# ProPrj___2025-10-04.net
KiCad netlist of a schematic drawn in EasyEDA Pro
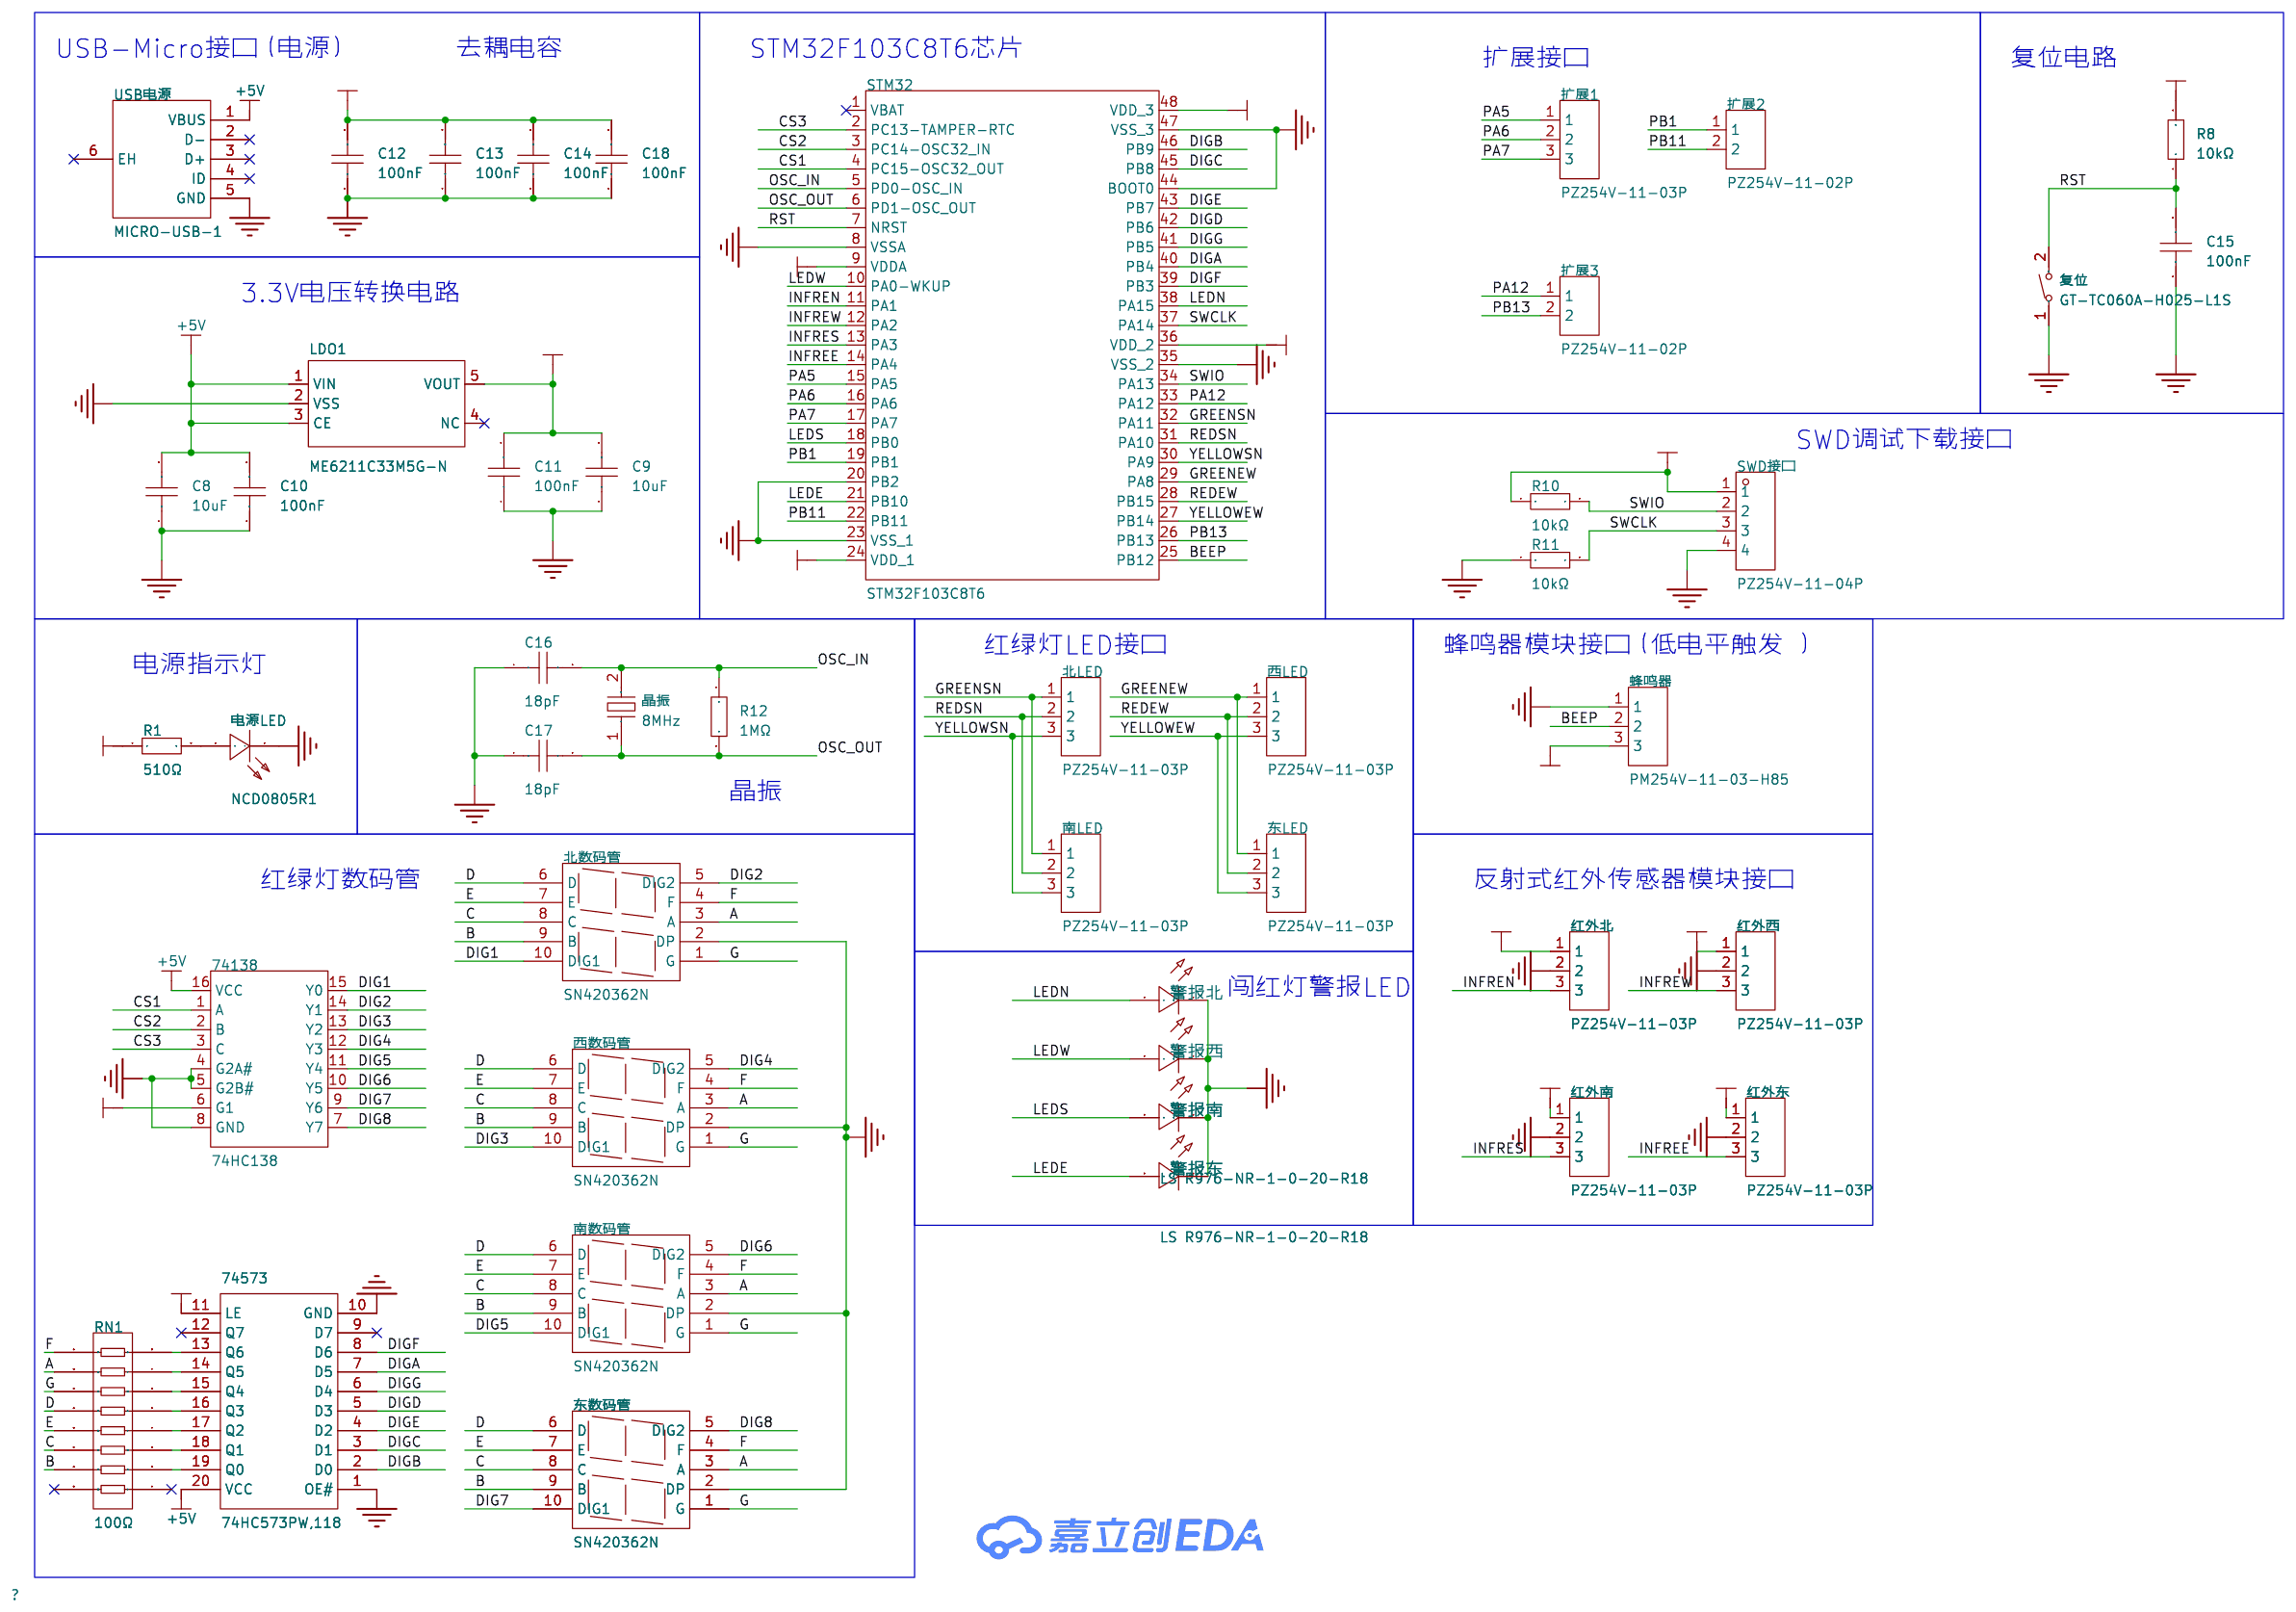
[diagram p0: schematic sheet]

(export (version "E")
  (design (tool "Eeschema 10.0.6"))
  (components
    (comp (ref "74138")
      (value "74HC138")
      (footprint "easyedapro:SOP-16_L10.0-W3.9-P1.27-LS6.0-BL")
      (description "供电电压:2V~6V;线路数:3~8;灌电流(IOL):5.2mA;拉电流(IOH):5.2mA;")
      (fields (field (name "Manufacturer") "GR(国睿)"))
      (libsource (lib "easyedapro") (part "74HC138_C18164491"))
    )
    (comp (ref "74573")
      (value "74HC573PW,118")
      (footprint "easyedapro:TSSOP-20_L6.5-W4.4-P0.65-LS6.4-BL")
      (description "逻辑类型:D型锁存器;电源电压:2V~6V;通道数:8;传播延迟:14ns;")
      (fields (field (name "Manufacturer") "Nexperia(安世)"))
      (libsource (lib "easyedapro") (part "74HC573PW,118"))
    )
    (comp (ref "C8")
      (value "10uF")
      (footprint "easyedapro:C0805")
      (description "容值:10uF;精度:±10%;额定电压:25V;温度系数:X5R;")
      (fields
        (field (name "Manufacturer Part") "CGA0805X5R106K250MT")
        (field (name "Manufacturer") "HRE(芯声)")
      )
      (libsource (lib "easyedapro") (part "CGA0805X5R106K250MT"))
    )
    (comp (ref "C9")
      (value "10uF")
      (footprint "easyedapro:C0805")
      (description "容值:10uF;精度:±10%;额定电压:25V;温度系数:X5R;")
      (fields
        (field (name "Manufacturer Part") "CGA0805X5R106K250MT")
        (field (name "Manufacturer") "HRE(芯声)")
      )
      (libsource (lib "easyedapro") (part "CGA0805X5R106K250MT"))
    )
    (comp (ref "C10")
      (value "100nF")
      (footprint "easyedapro:C0805")
      (description "容值:100nF;精度:±10%;额定电压:50V;材质(温度系数):X7R;")
      (fields
        (field (name "Manufacturer Part") "CC0805KRX7R9BB104")
        (field (name "Manufacturer") "YAGEO(国巨)")
      )
      (libsource (lib "easyedapro") (part "CC0805KRX7R9BB104"))
    )
    (comp (ref "C11")
      (value "100nF")
      (footprint "easyedapro:C0805")
      (description "容值:100nF;精度:±10%;额定电压:50V;材质(温度系数):X7R;")
      (fields
        (field (name "Manufacturer Part") "CC0805KRX7R9BB104")
        (field (name "Manufacturer") "YAGEO(国巨)")
      )
      (libsource (lib "easyedapro") (part "CC0805KRX7R9BB104"))
    )
    (comp (ref "C12")
      (value "100nF")
      (footprint "easyedapro:C0805")
      (description "容值:100nF;精度:±10%;额定电压:50V;材质(温度系数):X7R;")
      (fields
        (field (name "Manufacturer Part") "CC0805KRX7R9BB104")
        (field (name "Manufacturer") "YAGEO(国巨)")
      )
      (libsource (lib "easyedapro") (part "CC0805KRX7R9BB104"))
    )
    (comp (ref "C13")
      (value "100nF")
      (footprint "easyedapro:C0805")
      (description "容值:100nF;精度:±10%;额定电压:50V;材质(温度系数):X7R;")
      (fields
        (field (name "Manufacturer Part") "CC0805KRX7R9BB104")
        (field (name "Manufacturer") "YAGEO(国巨)")
      )
      (libsource (lib "easyedapro") (part "CC0805KRX7R9BB104"))
    )
    (comp (ref "C14")
      (value "100nF")
      (footprint "easyedapro:C0805")
      (description "容值:100nF;精度:±10%;额定电压:50V;材质(温度系数):X7R;")
      (fields
        (field (name "Manufacturer Part") "CC0805KRX7R9BB104")
        (field (name "Manufacturer") "YAGEO(国巨)")
      )
      (libsource (lib "easyedapro") (part "CC0805KRX7R9BB104"))
    )
    (comp (ref "C15")
      (value "100nF")
      (footprint "easyedapro:C0805")
      (description "容值:100nF;精度:±10%;额定电压:50V;材质(温度系数):X7R;")
      (fields
        (field (name "Manufacturer Part") "CC0805KRX7R9BB104")
        (field (name "Manufacturer") "YAGEO(国巨)")
      )
      (libsource (lib "easyedapro") (part "CC0805KRX7R9BB104"))
    )
    (comp (ref "C16")
      (value "18pF")
      (footprint "easyedapro:C0805")
      (description "容值:18pF;精度:±5%;额定电压:50V;温度系数:C0G;")
      (fields
        (field (name "Manufacturer Part") "CGA0805C0G180J500HT")
        (field (name "Manufacturer") "HRE(芯声)")
      )
      (libsource (lib "easyedapro") (part "CGA0805C0G180J500HT"))
    )
    (comp (ref "C17")
      (value "18pF")
      (footprint "easyedapro:C0805")
      (description "容值:18pF;精度:±5%;额定电压:50V;温度系数:C0G;")
      (fields
        (field (name "Manufacturer Part") "CGA0805C0G180J500HT")
        (field (name "Manufacturer") "HRE(芯声)")
      )
      (libsource (lib "easyedapro") (part "CGA0805C0G180J500HT"))
    )
    (comp (ref "C18")
      (value "100nF")
      (footprint "easyedapro:C0805")
      (description "容值:100nF;精度:±10%;额定电压:50V;材质(温度系数):X7R;")
      (fields
        (field (name "Manufacturer Part") "CC0805KRX7R9BB104")
        (field (name "Manufacturer") "YAGEO(国巨)")
      )
      (libsource (lib "easyedapro") (part "CC0805KRX7R9BB104"))
    )
    (comp (ref "LDO1")
      (value "ME6211C33M5G-N")
      (footprint "easyedapro:SOT-23-5_L3.0-W1.7-P0.95-LS2.8-BL")
      (description "输出类型:固定;工作电压:6V;输出电压:3.3V;输出电流:500mA;电源纹波抑制比(PSRR):70dB@(1kHz)；62dB@(10kHz);输出极性:正极;")
      (fields (field (name "Manufacturer") "MICRONE(南京微盟)"))
      (libsource (lib "easyedapro") (part "ME6211C33M5G-N"))
    )
    (comp (ref "R1")
      (value "510Ω")
      (footprint "easyedapro:R0805")
      (description "电阻类型:厚膜电阻;阻值:510Ω;精度:±1%;功率:125mW;最大工作电压:150V;温度系数:±100ppm/°C;")
      (fields
        (field (name "Manufacturer Part") "0805W8F5100T5E")
        (field (name "Manufacturer") "UNI-ROYAL(厚声)")
      )
      (libsource (lib "easyedapro") (part "0805W8F5100T5E"))
    )
    (comp (ref "R8")
      (value "10kΩ")
      (footprint "easyedapro:R0805")
      (description "电阻类型:厚膜电阻;阻值:10kΩ;精度:±1%;功率:125mW;最大工作电压:150V;温度系数:±100ppm/°C;")
      (fields
        (field (name "Manufacturer Part") "0805W8F1002T5E")
        (field (name "Manufacturer") "UNI-ROYAL(厚声)")
      )
      (libsource (lib "easyedapro") (part "0805W8F1002T5E"))
    )
    (comp (ref "R10")
      (value "10kΩ")
      (footprint "easyedapro:R0805")
      (description "电阻类型:厚膜电阻;阻值:10kΩ;精度:±1%;功率:125mW;最大工作电压:150V;温度系数:±100ppm/°C;")
      (fields
        (field (name "Manufacturer Part") "0805W8F1002T5E")
        (field (name "Manufacturer") "UNI-ROYAL(厚声)")
      )
      (libsource (lib "easyedapro") (part "0805W8F1002T5E"))
    )
    (comp (ref "R11")
      (value "10kΩ")
      (footprint "easyedapro:R0805")
      (description "电阻类型:厚膜电阻;阻值:10kΩ;精度:±1%;功率:125mW;最大工作电压:150V;温度系数:±100ppm/°C;")
      (fields
        (field (name "Manufacturer Part") "0805W8F1002T5E")
        (field (name "Manufacturer") "UNI-ROYAL(厚声)")
      )
      (libsource (lib "easyedapro") (part "0805W8F1002T5E"))
    )
    (comp (ref "R12")
      (value "1MΩ")
      (footprint "easyedapro:R0805")
      (description "电阻类型:厚膜电阻;阻值:1MΩ;精度:±1%;功率:125mW;最大工作电压:150V;温度系数:±100ppm/°C;")
      (fields
        (field (name "Manufacturer Part") "0805W8F1004T5E")
        (field (name "Manufacturer") "UNI-ROYAL(厚声)")
      )
      (libsource (lib "easyedapro") (part "0805W8F1004T5E"))
    )
    (comp (ref "RN1")
      (value "100Ω")
      (footprint "easyedapro:RES-ARRAY-SMD_16P-L3.8-W1.6-P0.50-BL")
      (description "电阻器数:8;阻值:100Ω;精度:±5%;单个元件功率:63mW;温度系数:±100ppm/°C;")
      (fields (field (name "Manufacturer Part") "EXB2HV101JV") (field (name "Manufacturer") "PANASONIC(松下)"))
      (libsource (lib "easyedapro") (part "EXB2HV101JV"))
    )
    (comp (ref "STM32")
      (value "STM32F103C8T6")
      (footprint "easyedapro:LQFP-48_L7.0-W7.0-P0.50-LS9.0-BL")
      (description "CPU内核:ARM-M3;CPU最大主频:72MHz;应用领域:-;")
      (fields (field (name "Manufacturer") "ST(意法半导体)"))
      (libsource (lib "easyedapro") (part "STM32F103C8T6"))
    )
    (comp (ref "SWD接口")
      (value "PZ254V-11-04P")
      (footprint "easyedapro:HDR-TH_4P-P2.54-V-M")
      (fields (field (name "Manufacturer") "XFCN(兴飞)"))
      (libsource (lib "easyedapro") (part "PZ254V-11-04P_C2691448"))
    )
    (comp (ref "USB电源")
      (value "MICRO-USB-1")
      (footprint "easyedapro:MICRO-USB-SMD_C9900008946")
      (libsource (lib "easyedapro") (part "MICRO-USB-1"))
    )
    (comp (ref "东LED")
      (value "PZ254V-11-03P")
      (footprint "easyedapro:HDR-TH_3P-P2.54-V-M")
      (fields (field (name "Manufacturer") "XFCN(兴飞)"))
      (libsource (lib "easyedapro") (part "PZ254V-11-03P_C2937625"))
    )
    (comp (ref "东数码管")
      (value "SN420362N")
      (footprint "easyedapro:LED-SEG-TH_10P-L15.0-W14.0-P2.54-S10.16-BL")
      (description "数码管位数:2位;耗散功率(Pd):50mW;发光颜色:红色;LED极性:共阴极;数字/字母大小(英寸):0.36;")
      (fields (field (name "Manufacturer") "ARKLED(方舟)"))
      (libsource (lib "easyedapro") (part "SN420362N"))
    )
    (comp (ref "北LED")
      (value "PZ254V-11-03P")
      (footprint "easyedapro:HDR-TH_3P-P2.54-V-M")
      (fields (field (name "Manufacturer") "XFCN(兴飞)"))
      (libsource (lib "easyedapro") (part "PZ254V-11-03P_C2937625"))
    )
    (comp (ref "北数码管")
      (value "SN420362N")
      (footprint "easyedapro:LED-SEG-TH_10P-L15.0-W14.0-P2.54-S10.16-BL")
      (description "数码管位数:2位;耗散功率(Pd):50mW;发光颜色:红色;LED极性:共阴极;数字/字母大小(英寸):0.36;")
      (fields (field (name "Manufacturer") "ARKLED(方舟)"))
      (libsource (lib "easyedapro") (part "SN420362N"))
    )
    (comp (ref "南LED")
      (value "PZ254V-11-03P")
      (footprint "easyedapro:HDR-TH_3P-P2.54-V-M")
      (fields (field (name "Manufacturer") "XFCN(兴飞)"))
      (libsource (lib "easyedapro") (part "PZ254V-11-03P_C2937625"))
    )
    (comp (ref "南数码管")
      (value "SN420362N")
      (footprint "easyedapro:LED-SEG-TH_10P-L15.0-W14.0-P2.54-S10.16-BL")
      (description "数码管位数:2位;耗散功率(Pd):50mW;发光颜色:红色;LED极性:共阴极;数字/字母大小(英寸):0.36;")
      (fields (field (name "Manufacturer") "ARKLED(方舟)"))
      (libsource (lib "easyedapro") (part "SN420362N"))
    )
    (comp (ref "复位")
      (value "GT-TC060A-H025-L1S")
      (footprint "easyedapro:SW-SMD_L6.1-W3.5-LS8.0")
      (description "电路结构:单刀单掷;作用力:1.6N;安装方式:立贴;带支架:不带;触点电流:50mA;额定电压(AC):12V;额定电压(DC):12V;绝缘电阻:100MΩ;带灯:无;机械寿命:10万次;")
      (fields (field (name "Manufacturer") "G-Switch(品赞)"))
      (libsource (lib "easyedapro") (part "GT-TC060A-H025-L1S"))
    )
    (comp (ref "扩展1")
      (value "PZ254V-11-03P")
      (footprint "easyedapro:HDR-TH_3P-P2.54-V-M")
      (fields (field (name "Manufacturer") "XFCN(兴飞)"))
      (libsource (lib "easyedapro") (part "PZ254V-11-03P_C2937625"))
    )
    (comp (ref "扩展2")
      (value "PZ254V-11-02P")
      (footprint "easyedapro:HDR-TH_2P-P2.54-V-M")
      (fields (field (name "Manufacturer") "XFCN(兴飞)"))
      (libsource (lib "easyedapro") (part "PZ254V-11-02P"))
    )
    (comp (ref "扩展3")
      (value "PZ254V-11-02P")
      (footprint "easyedapro:HDR-TH_2P-P2.54-V-M")
      (fields (field (name "Manufacturer") "XFCN(兴飞)"))
      (libsource (lib "easyedapro") (part "PZ254V-11-02P"))
    )
    (comp (ref "晶振")
      (value "8MHz")
      (footprint "easyedapro:HC-49US_L11.5-W4.5-P4.88")
      (description "频率:8MHz;常温频差:±20ppm;负载电容:18pF;频率稳定度(全温):±50ppm;")
      (fields (field (name "Manufacturer Part") "ABL-8.000MHZ-B2-T") (field (name "Manufacturer") "ABRACON"))
      (libsource (lib "easyedapro") (part "ABL-8.000MHZ-B2-T"))
    )
    (comp (ref "电源LED")
      (value "NCD0805R1")
      (footprint "easyedapro:LED0805-R-RD")
      (fields (field (name "Manufacturer") "国星光电"))
      (libsource (lib "easyedapro") (part "FC-2012HRK-620D"))
    )
    (comp (ref "红外东")
      (value "PZ254V-11-03P")
      (footprint "easyedapro:HDR-TH_3P-P2.54-V-M")
      (fields (field (name "Manufacturer") "XFCN(兴飞)"))
      (libsource (lib "easyedapro") (part "PZ254V-11-03P_C2937625"))
    )
    (comp (ref "红外北")
      (value "PZ254V-11-03P")
      (footprint "easyedapro:HDR-TH_3P-P2.54-V-M")
      (fields (field (name "Manufacturer") "XFCN(兴飞)"))
      (libsource (lib "easyedapro") (part "PZ254V-11-03P_C2937625"))
    )
    (comp (ref "红外南")
      (value "PZ254V-11-03P")
      (footprint "easyedapro:HDR-TH_3P-P2.54-V-M")
      (fields (field (name "Manufacturer") "XFCN(兴飞)"))
      (libsource (lib "easyedapro") (part "PZ254V-11-03P_C2937625"))
    )
    (comp (ref "红外西")
      (value "PZ254V-11-03P")
      (footprint "easyedapro:HDR-TH_3P-P2.54-V-M")
      (fields (field (name "Manufacturer") "XFCN(兴飞)"))
      (libsource (lib "easyedapro") (part "PZ254V-11-03P_C2937625"))
    )
    (comp (ref "蜂鸣器")
      (value "PM254V-11-03-H85")
      (footprint "easyedapro:HDR-TH_3P-P2.54-V-F")
      (description "插孔结构:1x3P;间距:2.54mm;行距:-;安装类型:直插;排数:单排;总孔位数:3P;塑高:-;触头材质:黄铜;触头镀层:-;")
      (fields (field (name "Manufacturer") "XFCN(兴飞)"))
      (libsource (lib "easyedapro") (part "PM254V-11-03-H85"))
    )
    (comp (ref "西LED")
      (value "PZ254V-11-03P")
      (footprint "easyedapro:HDR-TH_3P-P2.54-V-M")
      (fields (field (name "Manufacturer") "XFCN(兴飞)"))
      (libsource (lib "easyedapro") (part "PZ254V-11-03P_C2937625"))
    )
    (comp (ref "西数码管")
      (value "SN420362N")
      (footprint "easyedapro:LED-SEG-TH_10P-L15.0-W14.0-P2.54-S10.16-BL")
      (description "数码管位数:2位;耗散功率(Pd):50mW;发光颜色:红色;LED极性:共阴极;数字/字母大小(英寸):0.36;")
      (fields (field (name "Manufacturer") "ARKLED(方舟)"))
      (libsource (lib "easyedapro") (part "SN420362N"))
    )
    (comp (ref "警报东")
      (value "LS R976-NR-1-0-20-R18")
      (footprint "easyedapro:LED_0805")
      (fields (field (name "Manufacturer") "OSRAM(欧司朗)"))
      (libsource (lib "easyedapro") (part "LED_R"))
    )
    (comp (ref "警报北")
      (value "北")
      (footprint "easyedapro:LED_0805")
      (libsource (lib "easyedapro") (part "LED_R"))
    )
    (comp (ref "警报南")
      (value "LS R976-NR-1-0-20-R18")
      (footprint "easyedapro:LED_0805")
      (fields (field (name "Manufacturer") "OSRAM(欧司朗)"))
      (libsource (lib "easyedapro") (part "LED_R"))
    )
    (comp (ref "警报西")
      (value "西")
      (footprint "easyedapro:LED_0805")
      (libsource (lib "easyedapro") (part "LED_R"))
    )
  )
  (nets
    (net (code "1") (name "+5V") (class "Default")
      (node (ref "74138") (pin "16") (pinfunction "VCC_16") (pintype "unspecified"))
      (node (ref "74573") (pin "20") (pinfunction "VCC_20") (pintype "unspecified"))
      (node (ref "C10") (pin "2") (pinfunction "2_2") (pintype "unspecified"))
      (node (ref "C8") (pin "2") (pinfunction "2_2") (pintype "unspecified"))
      (node (ref "LDO1") (pin "1") (pinfunction "VIN_1") (pintype "unspecified"))
      (node (ref "LDO1") (pin "3") (pinfunction "CE_3") (pintype "unspecified"))
      (node (ref "USB电源") (pin "1") (pinfunction "VBUS_1") (pintype "input"))
    )
    (net (code "2") (name "/A") (class "Default")
      (node (ref "RN1") (pin "10") (pinfunction "10_10") (pintype "unspecified"))
      (node (ref "东数码管") (pin "3") (pinfunction "A_3") (pintype "unspecified"))
      (node (ref "北数码管") (pin "3") (pinfunction "A_3") (pintype "unspecified"))
      (node (ref "南数码管") (pin "3") (pinfunction "A_3") (pintype "unspecified"))
      (node (ref "西数码管") (pin "3") (pinfunction "A_3") (pintype "unspecified"))
    )
    (net (code "3") (name "/B") (class "Default")
      (node (ref "RN1") (pin "15") (pinfunction "15_15") (pintype "unspecified"))
      (node (ref "东数码管") (pin "9") (pinfunction "B_9") (pintype "unspecified"))
      (node (ref "北数码管") (pin "9") (pinfunction "B_9") (pintype "unspecified"))
      (node (ref "南数码管") (pin "9") (pinfunction "B_9") (pintype "unspecified"))
      (node (ref "西数码管") (pin "9") (pinfunction "B_9") (pintype "unspecified"))
    )
    (net (code "4") (name "/BEEP") (class "Default")
      (node (ref "STM32") (pin "25") (pinfunction "PB12_25") (pintype "unspecified"))
      (node (ref "蜂鸣器") (pin "2") (pinfunction "2_2") (pintype "unspecified"))
    )
    (net (code "5") (name "/C") (class "Default")
      (node (ref "RN1") (pin "14") (pinfunction "14_14") (pintype "unspecified"))
      (node (ref "东数码管") (pin "8") (pinfunction "C_8") (pintype "unspecified"))
      (node (ref "北数码管") (pin "8") (pinfunction "C_8") (pintype "unspecified"))
      (node (ref "南数码管") (pin "8") (pinfunction "C_8") (pintype "unspecified"))
      (node (ref "西数码管") (pin "8") (pinfunction "C_8") (pintype "unspecified"))
    )
    (net (code "6") (name "/CS1") (class "Default")
      (node (ref "74138") (pin "1") (pinfunction "A_1") (pintype "unspecified"))
      (node (ref "STM32") (pin "4") (pinfunction "PC15-OSC32_OUT_4") (pintype "unspecified"))
    )
    (net (code "7") (name "/CS2") (class "Default")
      (node (ref "74138") (pin "2") (pinfunction "B_2") (pintype "unspecified"))
      (node (ref "STM32") (pin "3") (pinfunction "PC14-OSC32_IN_3") (pintype "unspecified"))
    )
    (net (code "8") (name "/CS3") (class "Default")
      (node (ref "74138") (pin "3") (pinfunction "C_3") (pintype "unspecified"))
      (node (ref "STM32") (pin "2") (pinfunction "PC13-TAMPER-RTC_2") (pintype "unspecified"))
    )
    (net (code "9") (name "/D") (class "Default")
      (node (ref "RN1") (pin "12") (pinfunction "12_12") (pintype "unspecified"))
      (node (ref "东数码管") (pin "6") (pinfunction "D_6") (pintype "unspecified"))
      (node (ref "北数码管") (pin "6") (pinfunction "D_6") (pintype "unspecified"))
      (node (ref "南数码管") (pin "6") (pinfunction "D_6") (pintype "unspecified"))
      (node (ref "西数码管") (pin "6") (pinfunction "D_6") (pintype "unspecified"))
    )
    (net (code "10") (name "/DIG1") (class "Default")
      (node (ref "74138") (pin "15") (pinfunction "Y0_15") (pintype "unspecified"))
      (node (ref "北数码管") (pin "10") (pinfunction "DIG1_10") (pintype "unspecified"))
    )
    (net (code "11") (name "/DIG2") (class "Default")
      (node (ref "74138") (pin "14") (pinfunction "Y1_14") (pintype "unspecified"))
      (node (ref "北数码管") (pin "5") (pinfunction "DIG2_5") (pintype "unspecified"))
    )
    (net (code "12") (name "/DIG3") (class "Default")
      (node (ref "74138") (pin "13") (pinfunction "Y2_13") (pintype "unspecified"))
      (node (ref "西数码管") (pin "10") (pinfunction "DIG1_10") (pintype "unspecified"))
    )
    (net (code "13") (name "/DIG4") (class "Default")
      (node (ref "74138") (pin "12") (pinfunction "Y3_12") (pintype "unspecified"))
      (node (ref "西数码管") (pin "5") (pinfunction "DIG2_5") (pintype "unspecified"))
    )
    (net (code "14") (name "/DIG5") (class "Default")
      (node (ref "74138") (pin "11") (pinfunction "Y4_11") (pintype "unspecified"))
      (node (ref "南数码管") (pin "10") (pinfunction "DIG1_10") (pintype "unspecified"))
    )
    (net (code "15") (name "/DIG6") (class "Default")
      (node (ref "74138") (pin "10") (pinfunction "Y5_10") (pintype "unspecified"))
      (node (ref "南数码管") (pin "5") (pinfunction "DIG2_5") (pintype "unspecified"))
    )
    (net (code "16") (name "/DIG7") (class "Default")
      (node (ref "74138") (pin "9") (pinfunction "Y6_9") (pintype "unspecified"))
      (node (ref "东数码管") (pin "10") (pinfunction "DIG1_10") (pintype "unspecified"))
    )
    (net (code "17") (name "/DIG8") (class "Default")
      (node (ref "74138") (pin "7") (pinfunction "Y7_7") (pintype "unspecified"))
      (node (ref "东数码管") (pin "5") (pinfunction "DIG2_5") (pintype "unspecified"))
    )
    (net (code "18") (name "/DIGA") (class "Default")
      (node (ref "74573") (pin "7") (pinfunction "D5_7") (pintype "unspecified"))
      (node (ref "STM32") (pin "40") (pinfunction "PB4_40") (pintype "unspecified"))
    )
    (net (code "19") (name "/DIGB") (class "Default")
      (node (ref "74573") (pin "2") (pinfunction "D0_2") (pintype "unspecified"))
      (node (ref "STM32") (pin "46") (pinfunction "PB9_46") (pintype "unspecified"))
    )
    (net (code "20") (name "/DIGC") (class "Default")
      (node (ref "74573") (pin "3") (pinfunction "D1_3") (pintype "unspecified"))
      (node (ref "STM32") (pin "45") (pinfunction "PB8_45") (pintype "unspecified"))
    )
    (net (code "21") (name "/DIGD") (class "Default")
      (node (ref "74573") (pin "5") (pinfunction "D3_5") (pintype "unspecified"))
      (node (ref "STM32") (pin "42") (pinfunction "PB6_42") (pintype "unspecified"))
    )
    (net (code "22") (name "/DIGE") (class "Default")
      (node (ref "74573") (pin "4") (pinfunction "D2_4") (pintype "unspecified"))
      (node (ref "STM32") (pin "43") (pinfunction "PB7_43") (pintype "unspecified"))
    )
    (net (code "23") (name "/DIGF") (class "Default")
      (node (ref "74573") (pin "8") (pinfunction "D6_8") (pintype "unspecified"))
      (node (ref "STM32") (pin "39") (pinfunction "PB3_39") (pintype "unspecified"))
    )
    (net (code "24") (name "/DIGG") (class "Default")
      (node (ref "74573") (pin "6") (pinfunction "D4_6") (pintype "unspecified"))
      (node (ref "STM32") (pin "41") (pinfunction "PB5_41") (pintype "unspecified"))
    )
    (net (code "25") (name "/E") (class "Default")
      (node (ref "RN1") (pin "13") (pinfunction "13_13") (pintype "unspecified"))
      (node (ref "东数码管") (pin "7") (pinfunction "E_7") (pintype "unspecified"))
      (node (ref "北数码管") (pin "7") (pinfunction "E_7") (pintype "unspecified"))
      (node (ref "南数码管") (pin "7") (pinfunction "E_7") (pintype "unspecified"))
      (node (ref "西数码管") (pin "7") (pinfunction "E_7") (pintype "unspecified"))
    )
    (net (code "26") (name "/F") (class "Default")
      (node (ref "RN1") (pin "9") (pinfunction "9_9") (pintype "unspecified"))
      (node (ref "东数码管") (pin "4") (pinfunction "F_4") (pintype "unspecified"))
      (node (ref "北数码管") (pin "4") (pinfunction "F_4") (pintype "unspecified"))
      (node (ref "南数码管") (pin "4") (pinfunction "F_4") (pintype "unspecified"))
      (node (ref "西数码管") (pin "4") (pinfunction "F_4") (pintype "unspecified"))
    )
    (net (code "27") (name "/G") (class "Default")
      (node (ref "RN1") (pin "11") (pinfunction "11_11") (pintype "unspecified"))
      (node (ref "东数码管") (pin "1") (pinfunction "G_1") (pintype "unspecified"))
      (node (ref "北数码管") (pin "1") (pinfunction "G_1") (pintype "unspecified"))
      (node (ref "南数码管") (pin "1") (pinfunction "G_1") (pintype "unspecified"))
      (node (ref "西数码管") (pin "1") (pinfunction "G_1") (pintype "unspecified"))
    )
    (net (code "28") (name "/GREENEW") (class "Default")
      (node (ref "STM32") (pin "29") (pinfunction "PA8_29") (pintype "unspecified"))
      (node (ref "东LED") (pin "1") (pinfunction "1_1") (pintype "unspecified"))
      (node (ref "西LED") (pin "1") (pinfunction "1_1") (pintype "unspecified"))
    )
    (net (code "29") (name "/GREENSN") (class "Default")
      (node (ref "STM32") (pin "32") (pinfunction "PA11_32") (pintype "unspecified"))
      (node (ref "北LED") (pin "1") (pinfunction "1_1") (pintype "unspecified"))
      (node (ref "南LED") (pin "1") (pinfunction "1_1") (pintype "unspecified"))
    )
    (net (code "30") (name "/INFREE") (class "Default")
      (node (ref "STM32") (pin "14") (pinfunction "PA4_14") (pintype "unspecified"))
      (node (ref "红外东") (pin "3") (pinfunction "3_3") (pintype "unspecified"))
    )
    (net (code "31") (name "/INFREN") (class "Default")
      (node (ref "STM32") (pin "11") (pinfunction "PA1_11") (pintype "unspecified"))
      (node (ref "红外北") (pin "3") (pinfunction "3_3") (pintype "unspecified"))
    )
    (net (code "32") (name "/INFRES") (class "Default")
      (node (ref "STM32") (pin "13") (pinfunction "PA3_13") (pintype "unspecified"))
      (node (ref "红外南") (pin "3") (pinfunction "3_3") (pintype "unspecified"))
    )
    (net (code "33") (name "/INFREW") (class "Default")
      (node (ref "STM32") (pin "12") (pinfunction "PA2_12") (pintype "unspecified"))
      (node (ref "红外西") (pin "3") (pinfunction "3_3") (pintype "unspecified"))
    )
    (net (code "34") (name "/LEDE") (class "Default")
      (node (ref "STM32") (pin "21") (pinfunction "PB10_21") (pintype "unspecified"))
      (node (ref "警报东") (pin "2") (pinfunction "A_2") (pintype "input"))
    )
    (net (code "35") (name "/LEDN") (class "Default")
      (node (ref "STM32") (pin "38") (pinfunction "PA15_38") (pintype "unspecified"))
      (node (ref "警报北") (pin "2") (pinfunction "A_2") (pintype "input"))
    )
    (net (code "36") (name "/LEDS") (class "Default")
      (node (ref "STM32") (pin "18") (pinfunction "PB0_18") (pintype "unspecified"))
      (node (ref "警报南") (pin "2") (pinfunction "A_2") (pintype "input"))
    )
    (net (code "37") (name "/LEDW") (class "Default")
      (node (ref "STM32") (pin "10") (pinfunction "PA0-WKUP_10") (pintype "unspecified"))
      (node (ref "警报西") (pin "2") (pinfunction "A_2") (pintype "input"))
    )
    (net (code "38") (name "/OSC_IN") (class "Default")
      (node (ref "C16") (pin "2") (pinfunction "2_2") (pintype "unspecified"))
      (node (ref "R12") (pin "1") (pinfunction "1_1") (pintype "input"))
      (node (ref "STM32") (pin "5") (pinfunction "PD0-OSC_IN_5") (pintype "unspecified"))
      (node (ref "晶振") (pin "2") (pinfunction "2_2") (pintype "input"))
    )
    (net (code "39") (name "/OSC_OUT") (class "Default")
      (node (ref "C17") (pin "2") (pinfunction "2_2") (pintype "unspecified"))
      (node (ref "R12") (pin "2") (pinfunction "2_2") (pintype "input"))
      (node (ref "STM32") (pin "6") (pinfunction "PD1-OSC_OUT_6") (pintype "unspecified"))
      (node (ref "晶振") (pin "1") (pinfunction "1_1") (pintype "input"))
    )
    (net (code "40") (name "/PA5") (class "Default")
      (node (ref "STM32") (pin "15") (pinfunction "PA5_15") (pintype "unspecified"))
      (node (ref "扩展1") (pin "1") (pinfunction "1_1") (pintype "unspecified"))
    )
    (net (code "41") (name "/PA6") (class "Default")
      (node (ref "STM32") (pin "16") (pinfunction "PA6_16") (pintype "unspecified"))
      (node (ref "扩展1") (pin "2") (pinfunction "2_2") (pintype "unspecified"))
    )
    (net (code "42") (name "/PA7") (class "Default")
      (node (ref "STM32") (pin "17") (pinfunction "PA7_17") (pintype "unspecified"))
      (node (ref "扩展1") (pin "3") (pinfunction "3_3") (pintype "unspecified"))
    )
    (net (code "43") (name "/PA12") (class "Default")
      (node (ref "STM32") (pin "33") (pinfunction "PA12_33") (pintype "unspecified"))
      (node (ref "扩展3") (pin "1") (pinfunction "1_1") (pintype "unspecified"))
    )
    (net (code "44") (name "/PB1") (class "Default")
      (node (ref "STM32") (pin "19") (pinfunction "PB1_19") (pintype "unspecified"))
      (node (ref "扩展2") (pin "1") (pinfunction "1_1") (pintype "unspecified"))
    )
    (net (code "45") (name "/PB11") (class "Default")
      (node (ref "STM32") (pin "22") (pinfunction "PB11_22") (pintype "unspecified"))
      (node (ref "扩展2") (pin "2") (pinfunction "2_2") (pintype "unspecified"))
    )
    (net (code "46") (name "/PB13") (class "Default")
      (node (ref "STM32") (pin "26") (pinfunction "PB13_26") (pintype "unspecified"))
      (node (ref "扩展3") (pin "2") (pinfunction "2_2") (pintype "unspecified"))
    )
    (net (code "47") (name "/REDEW") (class "Default")
      (node (ref "STM32") (pin "28") (pinfunction "PB15_28") (pintype "unspecified"))
      (node (ref "东LED") (pin "2") (pinfunction "2_2") (pintype "unspecified"))
      (node (ref "西LED") (pin "2") (pinfunction "2_2") (pintype "unspecified"))
    )
    (net (code "48") (name "/REDSN") (class "Default")
      (node (ref "STM32") (pin "31") (pinfunction "PA10_31") (pintype "unspecified"))
      (node (ref "北LED") (pin "2") (pinfunction "2_2") (pintype "unspecified"))
      (node (ref "南LED") (pin "2") (pinfunction "2_2") (pintype "unspecified"))
    )
    (net (code "49") (name "/RST") (class "Default")
      (node (ref "C15") (pin "2") (pinfunction "2_2") (pintype "unspecified"))
      (node (ref "R8") (pin "1") (pinfunction "1_1") (pintype "input"))
      (node (ref "STM32") (pin "7") (pinfunction "NRST_7") (pintype "unspecified"))
      (node (ref "复位") (pin "2") (pinfunction "2_2") (pintype "unspecified"))
    )
    (net (code "50") (name "/SWCLK") (class "Default")
      (node (ref "R11") (pin "2") (pinfunction "2_2") (pintype "input"))
      (node (ref "STM32") (pin "37") (pinfunction "PA14_37") (pintype "unspecified"))
      (node (ref "SWD接口") (pin "3") (pinfunction "3_3") (pintype "unspecified"))
    )
    (net (code "51") (name "/SWIO") (class "Default")
      (node (ref "R10") (pin "2") (pinfunction "2_2") (pintype "input"))
      (node (ref "STM32") (pin "34") (pinfunction "PA13_34") (pintype "unspecified"))
      (node (ref "SWD接口") (pin "2") (pinfunction "2_2") (pintype "unspecified"))
    )
    (net (code "52") (name "/YELLOWEW") (class "Default")
      (node (ref "STM32") (pin "27") (pinfunction "PB14_27") (pintype "unspecified"))
      (node (ref "东LED") (pin "3") (pinfunction "3_3") (pintype "unspecified"))
      (node (ref "西LED") (pin "3") (pinfunction "3_3") (pintype "unspecified"))
    )
    (net (code "53") (name "/YELLOWSN") (class "Default")
      (node (ref "STM32") (pin "30") (pinfunction "PA9_30") (pintype "unspecified"))
      (node (ref "北LED") (pin "3") (pinfunction "3_3") (pintype "unspecified"))
      (node (ref "南LED") (pin "3") (pinfunction "3_3") (pintype "unspecified"))
    )
    (net (code "54") (name "GND") (class "Default")
      (node (ref "74138") (pin "4") (pinfunction "G2A#_4") (pintype "unspecified"))
      (node (ref "74138") (pin "5") (pinfunction "G2B#_5") (pintype "unspecified"))
      (node (ref "74138") (pin "8") (pinfunction "GND_8") (pintype "unspecified"))
      (node (ref "74573") (pin "1") (pinfunction "OE#_1") (pintype "unspecified"))
      (node (ref "74573") (pin "10") (pinfunction "GND_10") (pintype "unspecified"))
      (node (ref "C10") (pin "1") (pinfunction "1_1") (pintype "unspecified"))
      (node (ref "C11") (pin "1") (pinfunction "1_1") (pintype "unspecified"))
      (node (ref "C12") (pin "1") (pinfunction "1_1") (pintype "unspecified"))
      (node (ref "C13") (pin "1") (pinfunction "1_1") (pintype "unspecified"))
      (node (ref "C14") (pin "1") (pinfunction "1_1") (pintype "unspecified"))
      (node (ref "C15") (pin "1") (pinfunction "1_1") (pintype "unspecified"))
      (node (ref "C16") (pin "1") (pinfunction "1_1") (pintype "unspecified"))
      (node (ref "C17") (pin "1") (pinfunction "1_1") (pintype "unspecified"))
      (node (ref "C18") (pin "1") (pinfunction "1_1") (pintype "unspecified"))
      (node (ref "C8") (pin "1") (pinfunction "1_1") (pintype "unspecified"))
      (node (ref "C9") (pin "1") (pinfunction "1_1") (pintype "unspecified"))
      (node (ref "LDO1") (pin "2") (pinfunction "VSS_2") (pintype "unspecified"))
      (node (ref "R11") (pin "1") (pinfunction "1_1") (pintype "input"))
      (node (ref "STM32") (pin "20") (pinfunction "PB2_20") (pintype "unspecified"))
      (node (ref "STM32") (pin "23") (pinfunction "VSS_1_23") (pintype "unspecified"))
      (node (ref "STM32") (pin "35") (pinfunction "VSS_2_35") (pintype "unspecified"))
      (node (ref "STM32") (pin "44") (pinfunction "BOOT0_44") (pintype "unspecified"))
      (node (ref "STM32") (pin "47") (pinfunction "VSS_3_47") (pintype "unspecified"))
      (node (ref "STM32") (pin "8") (pinfunction "VSSA_8") (pintype "unspecified"))
      (node (ref "SWD接口") (pin "4") (pinfunction "4_4") (pintype "unspecified"))
      (node (ref "USB电源") (pin "5") (pinfunction "GND_5") (pintype "input"))
      (node (ref "东数码管") (pin "2") (pinfunction "DP_2") (pintype "unspecified"))
      (node (ref "北数码管") (pin "2") (pinfunction "DP_2") (pintype "unspecified"))
      (node (ref "南数码管") (pin "2") (pinfunction "DP_2") (pintype "unspecified"))
      (node (ref "复位") (pin "1") (pinfunction "1_1") (pintype "unspecified"))
      (node (ref "电源LED") (pin "2") (pinfunction "-_2") (pintype "unspecified"))
      (node (ref "红外东") (pin "2") (pinfunction "2_2") (pintype "unspecified"))
      (node (ref "红外北") (pin "2") (pinfunction "2_2") (pintype "unspecified"))
      (node (ref "红外南") (pin "2") (pinfunction "2_2") (pintype "unspecified"))
      (node (ref "红外西") (pin "2") (pinfunction "2_2") (pintype "unspecified"))
      (node (ref "蜂鸣器") (pin "1") (pinfunction "1_1") (pintype "unspecified"))
      (node (ref "西数码管") (pin "2") (pinfunction "DP_2") (pintype "unspecified"))
      (node (ref "警报东") (pin "1") (pinfunction "C_1") (pintype "input"))
      (node (ref "警报北") (pin "1") (pinfunction "C_1") (pintype "input"))
      (node (ref "警报南") (pin "1") (pinfunction "C_1") (pintype "input"))
      (node (ref "警报西") (pin "1") (pinfunction "C_1") (pintype "input"))
    )
    (net (code "55") (name "Net-(74573-Q0)") (class "Default")
      (node (ref "74573") (pin "19") (pinfunction "Q0_19") (pintype "unspecified"))
      (node (ref "RN1") (pin "2") (pinfunction "2_2") (pintype "unspecified"))
    )
    (net (code "56") (name "Net-(74573-Q1)") (class "Default")
      (node (ref "74573") (pin "18") (pinfunction "Q1_18") (pintype "unspecified"))
      (node (ref "RN1") (pin "3") (pinfunction "3_3") (pintype "unspecified"))
    )
    (net (code "57") (name "Net-(74573-Q2)") (class "Default")
      (node (ref "74573") (pin "17") (pinfunction "Q2_17") (pintype "unspecified"))
      (node (ref "RN1") (pin "4") (pinfunction "4_4") (pintype "unspecified"))
    )
    (net (code "58") (name "Net-(74573-Q3)") (class "Default")
      (node (ref "74573") (pin "16") (pinfunction "Q3_16") (pintype "unspecified"))
      (node (ref "RN1") (pin "5") (pinfunction "5_5") (pintype "unspecified"))
    )
    (net (code "59") (name "Net-(74573-Q4)") (class "Default")
      (node (ref "74573") (pin "15") (pinfunction "Q4_15") (pintype "unspecified"))
      (node (ref "RN1") (pin "6") (pinfunction "6_6") (pintype "unspecified"))
    )
    (net (code "60") (name "Net-(74573-Q5)") (class "Default")
      (node (ref "74573") (pin "14") (pinfunction "Q5_14") (pintype "unspecified"))
      (node (ref "RN1") (pin "7") (pinfunction "7_7") (pintype "unspecified"))
    )
    (net (code "61") (name "Net-(74573-Q6)") (class "Default")
      (node (ref "74573") (pin "13") (pinfunction "Q6_13") (pintype "unspecified"))
      (node (ref "RN1") (pin "8") (pinfunction "8_8") (pintype "unspecified"))
    )
    (net (code "62") (name "Net-(电源LED-+)") (class "Default")
      (node (ref "R1") (pin "2") (pinfunction "2_2") (pintype "input"))
      (node (ref "电源LED") (pin "1") (pinfunction "+_1") (pintype "unspecified"))
    )
    (net (code "63") (name "VCC_3V3") (class "Default")
      (node (ref "74138") (pin "6") (pinfunction "G1_6") (pintype "unspecified"))
      (node (ref "74573") (pin "11") (pinfunction "LE_11") (pintype "unspecified"))
      (node (ref "C11") (pin "2") (pinfunction "2_2") (pintype "unspecified"))
      (node (ref "C12") (pin "2") (pinfunction "2_2") (pintype "unspecified"))
      (node (ref "C13") (pin "2") (pinfunction "2_2") (pintype "unspecified"))
      (node (ref "C14") (pin "2") (pinfunction "2_2") (pintype "unspecified"))
      (node (ref "C18") (pin "2") (pinfunction "2_2") (pintype "unspecified"))
      (node (ref "C9") (pin "2") (pinfunction "2_2") (pintype "unspecified"))
      (node (ref "LDO1") (pin "5") (pinfunction "VOUT_5") (pintype "unspecified"))
      (node (ref "R1") (pin "1") (pinfunction "1_1") (pintype "input"))
      (node (ref "R10") (pin "1") (pinfunction "1_1") (pintype "input"))
      (node (ref "R8") (pin "2") (pinfunction "2_2") (pintype "input"))
      (node (ref "STM32") (pin "24") (pinfunction "VDD_1_24") (pintype "unspecified"))
      (node (ref "STM32") (pin "36") (pinfunction "VDD_2_36") (pintype "unspecified"))
      (node (ref "STM32") (pin "48") (pinfunction "VDD_3_48") (pintype "unspecified"))
      (node (ref "STM32") (pin "9") (pinfunction "VDDA_9") (pintype "unspecified"))
      (node (ref "SWD接口") (pin "1") (pinfunction "1_1") (pintype "unspecified"))
      (node (ref "红外东") (pin "1") (pinfunction "1_1") (pintype "unspecified"))
      (node (ref "红外北") (pin "1") (pinfunction "1_1") (pintype "unspecified"))
      (node (ref "红外南") (pin "1") (pinfunction "1_1") (pintype "unspecified"))
      (node (ref "红外西") (pin "1") (pinfunction "1_1") (pintype "unspecified"))
      (node (ref "蜂鸣器") (pin "3") (pinfunction "3_3") (pintype "unspecified"))
    )
    (net (code "64") (name "unconnected-(74573-D7-Pad9)") (class "Default")
      (node (ref "74573") (pin "9") (pinfunction "D7_9") (pintype "unspecified+no_connect"))
    )
    (net (code "65") (name "unconnected-(74573-Q7-Pad12)") (class "Default")
      (node (ref "74573") (pin "12") (pinfunction "Q7_12") (pintype "unspecified+no_connect"))
    )
    (net (code "66") (name "unconnected-(LDO1-NC-Pad4)") (class "Default")
      (node (ref "LDO1") (pin "4") (pinfunction "NC_4") (pintype "unspecified+no_connect"))
    )
    (net (code "67") (name "unconnected-(RN1-Pad1)") (class "Default")
      (node (ref "RN1") (pin "1") (pinfunction "1_1") (pintype "unspecified+no_connect"))
    )
    (net (code "68") (name "unconnected-(RN1-Pad16)") (class "Default")
      (node (ref "RN1") (pin "16") (pinfunction "16_16") (pintype "unspecified+no_connect"))
    )
    (net (code "69") (name "unconnected-(STM32-VBAT-Pad1)") (class "Default")
      (node (ref "STM32") (pin "1") (pinfunction "VBAT_1") (pintype "unspecified+no_connect"))
    )
    (net (code "70") (name "unconnected-(USB电源-D+-Pad3)") (class "Default")
      (node (ref "USB电源") (pin "3") (pinfunction "D+_3") (pintype "input+no_connect"))
    )
    (net (code "71") (name "unconnected-(USB电源-D--Pad2)") (class "Default")
      (node (ref "USB电源") (pin "2") (pinfunction "D-_2") (pintype "input+no_connect"))
    )
    (net (code "72") (name "unconnected-(USB电源-EH-Pad6)") (class "Default")
      (node (ref "USB电源") (pin "6") (pinfunction "EH_6") (pintype "input+no_connect"))
    )
    (net (code "73") (name "unconnected-(USB电源-ID-Pad4)") (class "Default")
      (node (ref "USB电源") (pin "4") (pinfunction "ID_4") (pintype "input+no_connect"))
    )
  )
)
